# SERIALIZER.net
KiCad netlist of a schematic drawn in Altium Designer
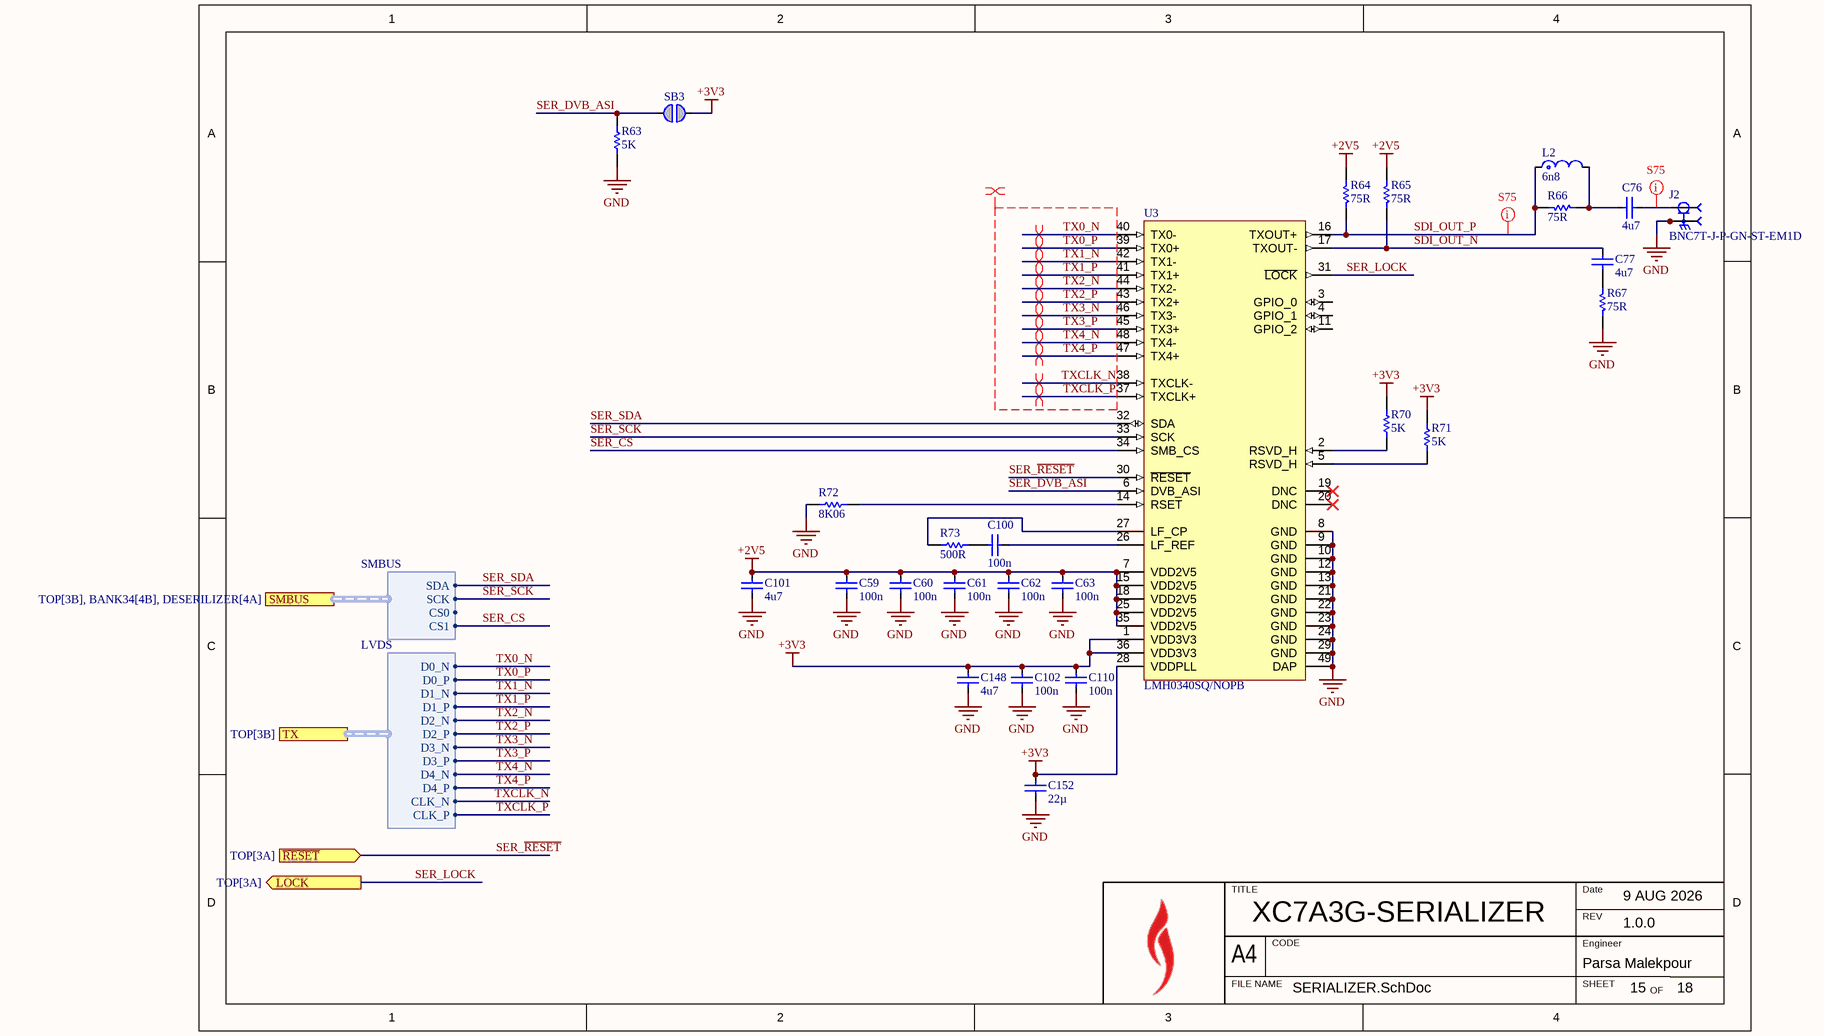
[diagram p0: SERIALIZER.SchDoc]

(export (version "E")
  (design (tool "Eeschema 10.0.6"))
  (components
    (comp (ref "C59")
      (value "100n")
      (footprint "FP-C1005-050-0_05-IPC_C")
      (description "MLCC 100nF ±10% 50V X7R SMD 0402")
      (fields (field (name "VOLTAGE") "50V") (field (name "TOLERANCE") "10%"))
      (libsource (lib "Schlib1") (part "C1005X7R1H104K050BB"))
    )
    (comp (ref "C60")
      (value "100n")
      (footprint "FP-C1005-050-0_05-IPC_C")
      (description "MLCC 100nF ±10% 50V X7R SMD 0402")
      (fields (field (name "VOLTAGE") "50V") (field (name "TOLERANCE") "10%"))
      (libsource (lib "Schlib1") (part "C1005X7R1H104K050BB"))
    )
    (comp (ref "C61")
      (value "100n")
      (footprint "FP-C1005-050-0_05-IPC_C")
      (description "MLCC 100nF ±10% 50V X7R SMD 0402")
      (fields (field (name "VOLTAGE") "50V") (field (name "TOLERANCE") "10%"))
      (libsource (lib "Schlib1") (part "C1005X7R1H104K050BB"))
    )
    (comp (ref "C62")
      (value "100n")
      (footprint "FP-C1005-050-0_05-IPC_C")
      (description "MLCC 100nF ±10% 50V X7R SMD 0402")
      (fields (field (name "VOLTAGE") "50V") (field (name "TOLERANCE") "10%"))
      (libsource (lib "Schlib1") (part "C1005X7R1H104K050BB"))
    )
    (comp (ref "C63")
      (value "100n")
      (footprint "FP-C1005-050-0_05-IPC_C")
      (description "MLCC 100nF ±10% 50V X7R SMD 0402")
      (fields (field (name "VOLTAGE") "50V") (field (name "TOLERANCE") "10%"))
      (libsource (lib "Schlib1") (part "C1005X7R1H104K050BB"))
    )
    (comp (ref "C76")
      (value "4u7")
      (footprint "FP-C1005-050-0_20-0_10-IPC_C")
      (description "4.7UF 10V X5R 0402")
      (fields (field (name "TOLERANCE") "10%") (field (name "PART NUMBER") "C1005X5R1A475K050BE"))
      (libsource (lib "Schlib1") (part "C1005X5R1A475K050BE"))
    )
    (comp (ref "C77")
      (value "4u7")
      (footprint "FP-C1005-050-0_20-0_10-IPC_C")
      (description "4.7UF 10V X5R 0402")
      (fields (field (name "TOLERANCE") "10%") (field (name "PART NUMBER") "C1005X5R1A475K050BE"))
      (libsource (lib "Schlib1") (part "C1005X5R1A475K050BE"))
    )
    (comp (ref "C100")
      (value "100n")
      (footprint "FP-C1005-050-0_05-IPC_C")
      (description "MLCC 100nF ±10% 50V X7R SMD 0402")
      (fields (field (name "VOLTAGE") "50V") (field (name "TOLERANCE") "10%"))
      (libsource (lib "Schlib1") (part "C1005X7R1H104K050BB"))
    )
    (comp (ref "C101")
      (value "4u7")
      (footprint "FP-C1005-050-0_20-0_10-IPC_C")
      (description "4.7UF 10V X5R 0402")
      (fields (field (name "TOLERANCE") "10%") (field (name "PART NUMBER") "C1005X5R1A475K050BE"))
      (libsource (lib "Schlib1") (part "C1005X5R1A475K050BE"))
    )
    (comp (ref "C102")
      (value "100n")
      (footprint "FP-C1005-050-0_05-IPC_C")
      (description "MLCC 100nF ±10% 50V X7R SMD 0402")
      (fields (field (name "VOLTAGE") "50V") (field (name "TOLERANCE") "10%"))
      (libsource (lib "Schlib1") (part "C1005X7R1H104K050BB"))
    )
    (comp (ref "C110")
      (value "100n")
      (footprint "FP-C1005-050-0_05-IPC_C")
      (description "MLCC 100nF ±10% 50V X7R SMD 0402")
      (fields (field (name "VOLTAGE") "50V") (field (name "TOLERANCE") "10%"))
      (libsource (lib "Schlib1") (part "C1005X7R1H104K050BB"))
    )
    (comp (ref "C148")
      (value "4u7")
      (footprint "FP-C1005-050-0_20-0_10-IPC_C")
      (description "4.7UF 10V X5R 0402")
      (fields (field (name "TOLERANCE") "10%") (field (name "PART NUMBER") "C1005X5R1A475K050BE"))
      (libsource (lib "Schlib1") (part "C1005X5R1A475K050BE"))
    )
    (comp (ref "C152")
      (value "22µ")
      (footprint "CAPC1608X100X20LL10")
      (description "MLCC 22 uF, ±20%, 6.3 V, -55 to 85 degC, 1608 (0603 Metric), RoHS, Tape and Reel")
      (fields
        (field (name "TOLERANCE") "±20%")
        (field (name "PCN PART NUMBER") "MLCCPartNumberChange30/Nov/2012")
      )
      (libsource (lib "Schlib1") (part "C1608X5R0J226M080AC"))
    )
    (comp (ref "J2")
      (value "BNC7T-J-P-GN-ST-EM1D")
      (footprint "SAMTEC_BNC7T-J-P-XX-ST-EM1D")
      (description "BNC Connector Jack, Female Socket 75Ohm Board Edge, End Launch; Panel Mount Solder")
      (fields (field (name "MF") "Samtec Inc."))
      (libsource (lib "Schlib1") (part "BNC7T-J-P-GN-ST-EM1D"))
    )
    (comp (ref "L2")
      (value "6n8")
      (footprint "FP-LQP03TG_02-MFG")
      (description "Film type RF Inductor 6.8nH ±5% 300mA 0.6Ω 0201 (0603)")
      (fields (field (name "TOLERANCE") "5%") (field (name "Comment") "LQP03TN6N8J02D"))
      (libsource (lib "Schlib1") (part "LQP03TN6N8J02D"))
    )
    (comp (ref "R63")
      (value "5K")
      (footprint "RESC1005X40X25NL05T10")
      (description "62.5mW Thick Film Resistors 50V ±100ppm/℃ ±1% 5kΩ 0402 Chip Resistor - Surface Mount ROHS")
      (fields (field (name "MANUFACTURER") "Yageo / Phycomp") (field (name "PART NUMBER") "RC0402FR-075KL"))
      (libsource (lib "Schlib1") (part "RES"))
    )
    (comp (ref "R64")
      (value "75R")
      (footprint "pcblib1:RESC1005X40X25LL05T10")
      (fields (field (name "MANUFACTURER") "Yageo / Phycomp") (field (name "PART NUMBER") "RC0402FR-0775RL"))
      (libsource (lib "Schlib1") (part "RC0402FR-0775RL"))
    )
    (comp (ref "R65")
      (value "75R")
      (footprint "pcblib1:RESC1005X40X25LL05T10")
      (fields (field (name "MANUFACTURER") "Yageo / Phycomp") (field (name "PART NUMBER") "RC0402FR-0775RL"))
      (libsource (lib "Schlib1") (part "RC0402FR-0775RL"))
    )
    (comp (ref "R66")
      (value "75R")
      (footprint "pcblib1:RESC1005X40X25LL05T10")
      (fields (field (name "MANUFACTURER") "Yageo / Phycomp") (field (name "PART NUMBER") "RC0402FR-0775RL"))
      (libsource (lib "Schlib1") (part "RC0402FR-0775RL"))
    )
    (comp (ref "R67")
      (value "75R")
      (footprint "pcblib1:RESC1005X40X25LL05T10")
      (fields (field (name "MANUFACTURER") "Yageo / Phycomp") (field (name "PART NUMBER") "RC0402FR-0775RL"))
      (libsource (lib "Schlib1") (part "RC0402FR-0775RL"))
    )
    (comp (ref "R70")
      (value "5K")
      (footprint "RESC1005X40X25NL05T10")
      (description "62.5mW Thick Film Resistors 50V ±100ppm/℃ ±1% 5kΩ 0402 Chip Resistor - Surface Mount ROHS")
      (fields (field (name "MANUFACTURER") "Yageo / Phycomp") (field (name "PART NUMBER") "RC0402FR-075KL"))
      (libsource (lib "Schlib1") (part "RES"))
    )
    (comp (ref "R71")
      (value "5K")
      (footprint "RESC1005X40X25NL05T10")
      (description "62.5mW Thick Film Resistors 50V ±100ppm/℃ ±1% 5kΩ 0402 Chip Resistor - Surface Mount ROHS")
      (fields (field (name "MANUFACTURER") "Yageo / Phycomp") (field (name "PART NUMBER") "RC0402FR-075KL"))
      (libsource (lib "Schlib1") (part "RES"))
    )
    (comp (ref "R72")
      (value "8K06")
      (footprint "RESC1005X40X25LL05T10")
      (fields (field (name "MANUFACTURER") "Yageo / Phycomp") (field (name "PART NUMBER") "RC0402FR-078K06L"))
      (libsource (lib "Schlib1") (part "RC0402FR-078K06L"))
    )
    (comp (ref "R73")
      (value "500R")
      (footprint "RESC1005X40X25NL05T10")
      (description "Res, 500R, 1%, 0.063W, Thin Film, 0402 Rohs Compliant: Yes")
      (fields (field (name "MANUFACTURER") "Yageo / Phycomp") (field (name "PART NUMBER") "RT0402FRE07500RL"))
      (libsource (lib "Schlib1") (part "RT0402FRE07500RL"))
    )
    (comp (ref "SB3")
      (value "Solderbridge")
      (footprint "Solderbridge")
      (fields (field (name "MANUFACTURER") "N.A."))
      (libsource (lib "ParsaLibrary") (part "Solderbridge_1"))
    )
    (comp (ref "U3")
      (value "LMH0340SQ/NOPB")
      (footprint "RHS0048A_V")
      (description "3 Gbps, HD, SD, DVB-ASI SDI Serializer and Driver with LVDS Interface, 48-pin LLP, Pb-Free")
      (fields (field (name "MANUFACTURER") "Texas Instruments"))
      (libsource (lib "Schlib1") (part "IN-SDZR-LMH0040SQ"))
    )
  )
  (nets
    (net (code "3") (name "+2V5") (class "Default")
      (node (ref "C101") (pin "2") (pinfunction "2_2") (pintype "passive"))
      (node (ref "C59") (pin "1") (pinfunction "1_1") (pintype "passive"))
      (node (ref "C60") (pin "1") (pinfunction "1_1") (pintype "passive"))
      (node (ref "C61") (pin "1") (pinfunction "1_1") (pintype "passive"))
      (node (ref "C62") (pin "1") (pinfunction "1_1") (pintype "passive"))
      (node (ref "C63") (pin "1") (pinfunction "1_1") (pintype "passive"))
      (node (ref "R64") (pin "2") (pinfunction "2_2") (pintype "passive"))
      (node (ref "R65") (pin "2") (pinfunction "2_2") (pintype "passive"))
      (node (ref "U3") (pin "15") (pinfunction "VDD2V5_15") (pintype "power_in"))
      (node (ref "U3") (pin "18") (pinfunction "VDD2V5_18") (pintype "power_in"))
      (node (ref "U3") (pin "25") (pinfunction "VDD2V5_25") (pintype "power_in"))
      (node (ref "U3") (pin "35") (pinfunction "VDD2V5_35") (pintype "power_in"))
      (node (ref "U3") (pin "7") (pinfunction "VDD2V5_7") (pintype "power_in"))
    )
    (net (code "4") (name "+3V3") (class "Default")
      (node (ref "C102") (pin "1") (pinfunction "1_1") (pintype "passive"))
      (node (ref "C110") (pin "1") (pinfunction "1_1") (pintype "passive"))
      (node (ref "C148") (pin "1") (pinfunction "1_1") (pintype "passive"))
      (node (ref "C152") (pin "1") (pinfunction "1_1") (pintype "passive"))
      (node (ref "R70") (pin "1") (pinfunction "1_1") (pintype "passive"))
      (node (ref "R71") (pin "1") (pinfunction "1_1") (pintype "passive"))
      (node (ref "SB3") (pin "1") (pinfunction "0_1") (pintype "passive"))
      (node (ref "U3") (pin "1") (pinfunction "VDD3V3_1") (pintype "power_in"))
      (node (ref "U3") (pin "28") (pinfunction "VDDPLL_28") (pintype "power_in"))
      (node (ref "U3") (pin "36") (pinfunction "VDD3V3_36") (pintype "power_in"))
    )
    (net (code "5") (name "/SDI_OUT_N") (class "Default")
      (node (ref "C77") (pin "2") (pinfunction "2_2") (pintype "passive"))
      (node (ref "R65") (pin "1") (pinfunction "1_1") (pintype "passive"))
      (node (ref "U3") (pin "17") (pinfunction "TXOUT-_17") (pintype "output"))
    )
    (net (code "6") (name "/SDI_OUT_P") (class "Default")
      (node (ref "L2") (pin "1") (pinfunction "1_1") (pintype "passive"))
      (node (ref "R64") (pin "1") (pinfunction "1_1") (pintype "passive"))
      (node (ref "R66") (pin "1") (pinfunction "1_1") (pintype "passive"))
      (node (ref "U3") (pin "16") (pinfunction "TXOUT+_16") (pintype "output"))
    )
    (net (code "7") (name "/SER_CS") (class "Default")
      (node (ref "U3") (pin "34") (pinfunction "SMB_CS_34") (pintype "input"))
    )
    (net (code "8") (name "/SER_DVB_ASI") (class "Default")
      (node (ref "R63") (pin "1") (pinfunction "1_1") (pintype "passive"))
      (node (ref "SB3") (pin "2") (pinfunction "1_2") (pintype "passive"))
      (node (ref "U3") (pin "6") (pinfunction "DVB_ASI_6") (pintype "input"))
    )
    (net (code "9") (name "/SER_LOCK") (class "Default")
      (node (ref "U3") (pin "31") (pinfunction "~{LOCK}_31") (pintype "output"))
    )
    (net (code "10") (name "/SER_SCK") (class "Default")
      (node (ref "U3") (pin "33") (pinfunction "SCK_33") (pintype "input"))
    )
    (net (code "11") (name "/SER_SDA") (class "Default")
      (node (ref "U3") (pin "32") (pinfunction "SDA_32") (pintype "bidirectional"))
    )
    (net (code "12") (name "/SER_~{RESET}") (class "Default")
      (node (ref "U3") (pin "30") (pinfunction "~{RESET}_30") (pintype "input"))
    )
    (net (code "13") (name "/TX0_N") (class "Default")
      (node (ref "U3") (pin "40") (pinfunction "TX0-_40") (pintype "input"))
    )
    (net (code "14") (name "/TX0_P") (class "Default")
      (node (ref "U3") (pin "39") (pinfunction "TX0+_39") (pintype "input"))
    )
    (net (code "15") (name "/TX1_N") (class "Default")
      (node (ref "U3") (pin "42") (pinfunction "TX1-_42") (pintype "input"))
    )
    (net (code "16") (name "/TX1_P") (class "Default")
      (node (ref "U3") (pin "41") (pinfunction "TX1+_41") (pintype "input"))
    )
    (net (code "17") (name "/TX2_N") (class "Default")
      (node (ref "U3") (pin "44") (pinfunction "TX2-_44") (pintype "input"))
    )
    (net (code "18") (name "/TX2_P") (class "Default")
      (node (ref "U3") (pin "43") (pinfunction "TX2+_43") (pintype "input"))
    )
    (net (code "19") (name "/TX3_N") (class "Default")
      (node (ref "U3") (pin "46") (pinfunction "TX3-_46") (pintype "input"))
    )
    (net (code "20") (name "/TX3_P") (class "Default")
      (node (ref "U3") (pin "45") (pinfunction "TX3+_45") (pintype "input"))
    )
    (net (code "21") (name "/TX4_N") (class "Default")
      (node (ref "U3") (pin "48") (pinfunction "TX4-_48") (pintype "input"))
    )
    (net (code "22") (name "/TX4_P") (class "Default")
      (node (ref "U3") (pin "47") (pinfunction "TX4+_47") (pintype "input"))
    )
    (net (code "23") (name "/TXCLK_N") (class "Default")
      (node (ref "U3") (pin "38") (pinfunction "TXCLK-_38") (pintype "input"))
    )
    (net (code "24") (name "/TXCLK_P") (class "Default")
      (node (ref "U3") (pin "37") (pinfunction "TXCLK+_37") (pintype "input"))
    )
    (net (code "27") (name "GND") (class "Default")
      (node (ref "C101") (pin "1") (pinfunction "1_1") (pintype "passive"))
      (node (ref "C102") (pin "2") (pinfunction "2_2") (pintype "passive"))
      (node (ref "C110") (pin "2") (pinfunction "2_2") (pintype "passive"))
      (node (ref "C148") (pin "2") (pinfunction "2_2") (pintype "passive"))
      (node (ref "C152") (pin "2") (pinfunction "2_2") (pintype "passive"))
      (node (ref "C59") (pin "2") (pinfunction "2_2") (pintype "passive"))
      (node (ref "C60") (pin "2") (pinfunction "2_2") (pintype "passive"))
      (node (ref "C61") (pin "2") (pinfunction "2_2") (pintype "passive"))
      (node (ref "C62") (pin "2") (pinfunction "2_2") (pintype "passive"))
      (node (ref "C63") (pin "2") (pinfunction "2_2") (pintype "passive"))
      (node (ref "J2") (pin "S1") (pinfunction "2_S1") (pintype "passive"))
      (node (ref "J2") (pin "S2") (pinfunction "2_S2") (pintype "passive"))
      (node (ref "J2") (pin "S3") (pinfunction "2_S3") (pintype "passive"))
      (node (ref "J2") (pin "S4") (pinfunction "2_S4") (pintype "passive"))
      (node (ref "R63") (pin "2") (pinfunction "2_2") (pintype "passive"))
      (node (ref "R67") (pin "2") (pinfunction "2_2") (pintype "passive"))
      (node (ref "R72") (pin "1") (pinfunction "1_1") (pintype "passive"))
      (node (ref "U3") (pin "10") (pinfunction "GND_10") (pintype "power_in"))
      (node (ref "U3") (pin "12") (pinfunction "GND_12") (pintype "power_in"))
      (node (ref "U3") (pin "13") (pinfunction "GND_13") (pintype "power_in"))
      (node (ref "U3") (pin "21") (pinfunction "GND_21") (pintype "power_in"))
      (node (ref "U3") (pin "22") (pinfunction "GND_22") (pintype "power_in"))
      (node (ref "U3") (pin "23") (pinfunction "GND_23") (pintype "power_in"))
      (node (ref "U3") (pin "24") (pinfunction "GND_24") (pintype "power_in"))
      (node (ref "U3") (pin "29") (pinfunction "GND_29") (pintype "power_in"))
      (node (ref "U3") (pin "49") (pinfunction "DAP_49") (pintype "power_in"))
      (node (ref "U3") (pin "8") (pinfunction "GND_8") (pintype "power_in"))
      (node (ref "U3") (pin "9") (pinfunction "GND_9") (pintype "power_in"))
    )
    (net (code "28") (name "Net-(C76-Pad1)") (class "Default")
      (node (ref "C76") (pin "1") (pinfunction "1_1") (pintype "passive"))
      (node (ref "L2") (pin "2") (pinfunction "2_2") (pintype "passive"))
      (node (ref "R66") (pin "2") (pinfunction "2_2") (pintype "passive"))
    )
    (net (code "29") (name "Net-(C76-Pad2)") (class "Default")
      (node (ref "C76") (pin "2") (pinfunction "2_2") (pintype "passive"))
      (node (ref "J2") (pin "1") (pinfunction "1_1") (pintype "passive"))
    )
    (net (code "30") (name "Net-(C77-Pad1)") (class "Default")
      (node (ref "C77") (pin "1") (pinfunction "1_1") (pintype "passive"))
      (node (ref "R67") (pin "1") (pinfunction "1_1") (pintype "passive"))
    )
    (net (code "31") (name "Net-(C100-Pad1)") (class "Default")
      (node (ref "C100") (pin "1") (pinfunction "1_1") (pintype "passive"))
      (node (ref "R73") (pin "2") (pinfunction "2_2") (pintype "passive"))
    )
    (net (code "32") (name "Net-(R70-Pad2)") (class "Default")
      (node (ref "R70") (pin "2") (pinfunction "2_2") (pintype "passive"))
      (node (ref "U3") (pin "2") (pinfunction "RSVD_H_2") (pintype "input"))
    )
    (net (code "33") (name "Net-(R71-Pad2)") (class "Default")
      (node (ref "R71") (pin "2") (pinfunction "2_2") (pintype "passive"))
      (node (ref "U3") (pin "5") (pinfunction "RSVD_H_5") (pintype "input"))
    )
    (net (code "34") (name "Net-(U3-LF_CP)") (class "Default")
      (node (ref "R73") (pin "1") (pinfunction "1_1") (pintype "passive"))
      (node (ref "U3") (pin "27") (pinfunction "LF_CP_27") (pintype "passive"))
    )
    (net (code "35") (name "Net-(U3-LF_REF)") (class "Default")
      (node (ref "C100") (pin "2") (pinfunction "2_2") (pintype "passive"))
      (node (ref "U3") (pin "26") (pinfunction "LF_REF_26") (pintype "passive"))
    )
    (net (code "36") (name "Net-(U3-RSET)") (class "Default")
      (node (ref "R72") (pin "2") (pinfunction "2_2") (pintype "passive"))
      (node (ref "U3") (pin "14") (pinfunction "RSET_14") (pintype "input"))
    )
    (net (code "37") (name "unconnected-(U3-DNC-Pad19)") (class "Default")
      (node (ref "U3") (pin "19") (pinfunction "DNC_19") (pintype "passive+no_connect"))
    )
    (net (code "38") (name "unconnected-(U3-DNC-Pad20)") (class "Default")
      (node (ref "U3") (pin "20") (pinfunction "DNC_20") (pintype "passive+no_connect"))
    )
    (net (code "39") (name "unconnected-(U3-GPIO_0-Pad3)") (class "Default")
      (node (ref "U3") (pin "3") (pinfunction "GPIO_0_3") (pintype "bidirectional"))
    )
    (net (code "40") (name "unconnected-(U3-GPIO_1-Pad4)") (class "Default")
      (node (ref "U3") (pin "4") (pinfunction "GPIO_1_4") (pintype "bidirectional"))
    )
    (net (code "41") (name "unconnected-(U3-GPIO_2-Pad11)") (class "Default")
      (node (ref "U3") (pin "11") (pinfunction "GPIO_2_11") (pintype "bidirectional"))
    )
  )
)
